# Synth.net
KiCad netlist of a schematic drawn in Altium Designer
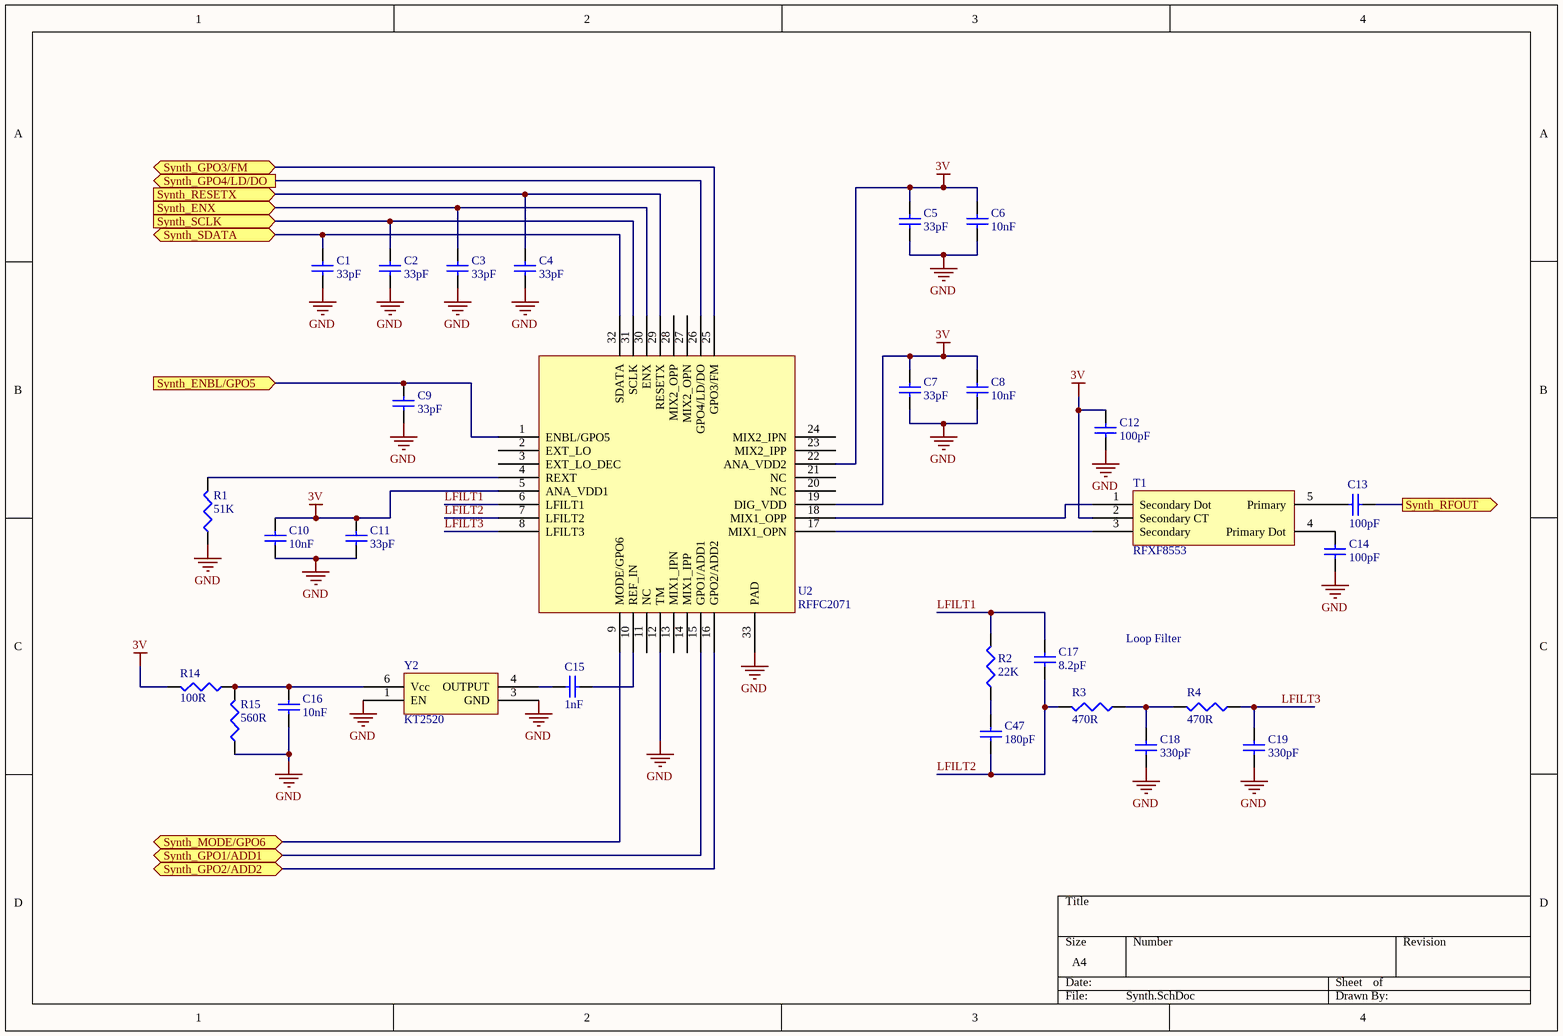
[diagram p0: Synth.SchDoc]

(export (version "E")
  (design (tool "Eeschema 10.0.6"))
  (components
    (comp (ref "C1")
      (value "33pF")
      (footprint "1608[0603]")
      (description "Capacitor (Semiconductor SIM Model)")
      (fields (field (name "Comment") "Cap Semi") (field (name "PUBLISHER") "Altium Limited"))
      (libsource (lib "Miscellaneous Devices") (part "Cap Semi"))
    )
    (comp (ref "C2")
      (value "33pF")
      (footprint "1608[0603]")
      (description "Capacitor (Semiconductor SIM Model)")
      (fields (field (name "Comment") "Cap Semi") (field (name "PUBLISHER") "Altium Limited"))
      (libsource (lib "Miscellaneous Devices") (part "Cap Semi"))
    )
    (comp (ref "C3")
      (value "33pF")
      (footprint "1608[0603]")
      (description "Capacitor (Semiconductor SIM Model)")
      (fields (field (name "Comment") "Cap Semi") (field (name "PUBLISHER") "Altium Limited"))
      (libsource (lib "Miscellaneous Devices") (part "Cap Semi"))
    )
    (comp (ref "C4")
      (value "33pF")
      (footprint "1608[0603]")
      (description "Capacitor (Semiconductor SIM Model)")
      (fields (field (name "Comment") "Cap Semi") (field (name "PUBLISHER") "Altium Limited"))
      (libsource (lib "Miscellaneous Devices") (part "Cap Semi"))
    )
    (comp (ref "C5")
      (value "33pF")
      (footprint "1608[0603]")
      (description "Capacitor (Semiconductor SIM Model)")
      (fields (field (name "Comment") "Cap Semi") (field (name "PUBLISHER") "Altium Limited"))
      (libsource (lib "Miscellaneous Devices") (part "Cap Semi"))
    )
    (comp (ref "C6")
      (value "10nF")
      (footprint "1608[0603]")
      (description "Capacitor (Semiconductor SIM Model)")
      (fields (field (name "Comment") "Cap Semi") (field (name "PUBLISHER") "Altium Limited"))
      (libsource (lib "Miscellaneous Devices") (part "Cap Semi"))
    )
    (comp (ref "C7")
      (value "33pF")
      (footprint "1608[0603]")
      (description "Capacitor (Semiconductor SIM Model)")
      (fields (field (name "Comment") "Cap Semi") (field (name "PUBLISHER") "Altium Limited"))
      (libsource (lib "Miscellaneous Devices") (part "Cap Semi"))
    )
    (comp (ref "C8")
      (value "10nF")
      (footprint "1608[0603]")
      (description "Capacitor (Semiconductor SIM Model)")
      (fields (field (name "Comment") "Cap Semi") (field (name "PUBLISHER") "Altium Limited"))
      (libsource (lib "Miscellaneous Devices") (part "Cap Semi"))
    )
    (comp (ref "C9")
      (value "33pF")
      (footprint "1608[0603]")
      (description "Capacitor (Semiconductor SIM Model)")
      (fields (field (name "Comment") "Cap Semi") (field (name "PUBLISHER") "Altium Limited"))
      (libsource (lib "Miscellaneous Devices") (part "Cap Semi"))
    )
    (comp (ref "C10")
      (value "10nF")
      (footprint "1608[0603]")
      (description "Capacitor (Semiconductor SIM Model)")
      (fields (field (name "Comment") "Cap Semi") (field (name "PUBLISHER") "Altium Limited"))
      (libsource (lib "Miscellaneous Devices") (part "Cap Semi"))
    )
    (comp (ref "C11")
      (value "33pF")
      (footprint "1608[0603]")
      (description "Capacitor (Semiconductor SIM Model)")
      (fields (field (name "Comment") "Cap Semi") (field (name "PUBLISHER") "Altium Limited"))
      (libsource (lib "Miscellaneous Devices") (part "Cap Semi"))
    )
    (comp (ref "C12")
      (value "100pF")
      (footprint "1608[0603]")
      (description "Capacitor (Semiconductor SIM Model)")
      (fields (field (name "Comment") "Cap Semi") (field (name "PUBLISHER") "Altium Limited"))
      (libsource (lib "Miscellaneous Devices") (part "Cap Semi"))
    )
    (comp (ref "C13")
      (value "100pF")
      (footprint "1608[0603]")
      (description "Capacitor (Semiconductor SIM Model)")
      (fields (field (name "Comment") "Cap Semi") (field (name "PUBLISHER") "Altium Limited"))
      (libsource (lib "Miscellaneous Devices") (part "Cap Semi"))
    )
    (comp (ref "C14")
      (value "100pF")
      (footprint "1608[0603]")
      (description "Capacitor (Semiconductor SIM Model)")
      (fields (field (name "Comment") "Cap Semi") (field (name "PUBLISHER") "Altium Limited"))
      (libsource (lib "Miscellaneous Devices") (part "Cap Semi"))
    )
    (comp (ref "C15")
      (value "1nF")
      (footprint "1608[0603]")
      (description "Capacitor (Semiconductor SIM Model)")
      (fields (field (name "Comment") "Cap Semi") (field (name "PUBLISHER") "Altium Limited"))
      (libsource (lib "Miscellaneous Devices") (part "Cap Semi"))
    )
    (comp (ref "C16")
      (value "10nF")
      (footprint "1608[0603]")
      (description "Capacitor (Semiconductor SIM Model)")
      (fields (field (name "Comment") "Cap Semi") (field (name "PUBLISHER") "Altium Limited"))
      (libsource (lib "Miscellaneous Devices") (part "Cap Semi"))
    )
    (comp (ref "C17")
      (value "8.2pF")
      (footprint "1608[0603]")
      (description "Capacitor (Semiconductor SIM Model)")
      (fields (field (name "Comment") "Cap Semi") (field (name "PUBLISHER") "Altium Limited"))
      (libsource (lib "Miscellaneous Devices") (part "Cap Semi"))
    )
    (comp (ref "C18")
      (value "330pF")
      (footprint "1608[0603]")
      (description "Capacitor (Semiconductor SIM Model)")
      (fields (field (name "Comment") "Cap Semi") (field (name "PUBLISHER") "Altium Limited"))
      (libsource (lib "Miscellaneous Devices") (part "Cap Semi"))
    )
    (comp (ref "C19")
      (value "330pF")
      (footprint "1608[0603]")
      (description "Capacitor (Semiconductor SIM Model)")
      (fields (field (name "Comment") "Cap Semi") (field (name "PUBLISHER") "Altium Limited"))
      (libsource (lib "Miscellaneous Devices") (part "Cap Semi"))
    )
    (comp (ref "C47")
      (value "180pF")
      (footprint "1608[0603]")
      (description "Capacitor (Semiconductor SIM Model)")
      (fields (field (name "Comment") "Cap Semi") (field (name "PUBLISHER") "Altium Limited"))
      (libsource (lib "Miscellaneous Devices") (part "Cap Semi"))
    )
    (comp (ref "R1")
      (value "51K")
      (footprint "J1-0603")
      (description "Resistor")
      (fields (field (name "Comment") "Res3") (field (name "PUBLISHER") "Altium Limited"))
      (libsource (lib "Miscellaneous Devices") (part "Res3"))
    )
    (comp (ref "R2")
      (value "22K")
      (footprint "J1-0603")
      (description "Resistor")
      (fields (field (name "Comment") "Res3") (field (name "PUBLISHER") "Altium Limited"))
      (libsource (lib "Miscellaneous Devices") (part "Res3"))
    )
    (comp (ref "R3")
      (value "470R")
      (footprint "J1-0603")
      (description "Resistor")
      (fields (field (name "Comment") "Res3") (field (name "PUBLISHER") "Altium Limited"))
      (libsource (lib "Miscellaneous Devices") (part "Res3"))
    )
    (comp (ref "R4")
      (value "470R")
      (footprint "J1-0603")
      (description "Resistor")
      (fields (field (name "Comment") "Res3") (field (name "PUBLISHER") "Altium Limited"))
      (libsource (lib "Miscellaneous Devices") (part "Res3"))
    )
    (comp (ref "R14")
      (value "100R")
      (footprint "J1-0603")
      (description "Resistor")
      (fields (field (name "Comment") "Res3") (field (name "PUBLISHER") "Altium Limited"))
      (libsource (lib "Miscellaneous Devices") (part "Res3"))
    )
    (comp (ref "R15")
      (value "560R")
      (footprint "J1-0603")
      (description "Resistor")
      (fields (field (name "Comment") "Res3") (field (name "PUBLISHER") "Altium Limited"))
      (libsource (lib "Miscellaneous Devices") (part "Res3"))
    )
    (comp (ref "T1")
      (value "RFXF8553")
      (footprint "RFXF8553")
      (description "1:4 SMT TRANSFORMER")
      (libsource (lib "Logic_RF_Component_Symbols") (part "RFXF8553"))
    )
    (comp (ref "U2")
      (value "RFFC2071")
      (footprint "QFN50P500X500-32WAL")
      (description "2.7GHz RF SYNTHESIZER/VCO WITH INTEGRATED RF MIXER")
      (libsource (lib "Logic_RF_Component_Symbols") (part "RFFC2071"))
    )
    (comp (ref "Y2")
      (value "KT2520")
      (footprint "KT2520")
      (description "Temperature-Compensated Crystal Oscillator (TCXO) KT2520")
      (libsource (lib "Logic_RF_Component_Symbols") (part "KT2520"))
    )
  )
  (nets
    (net (code "1") (name "/LFILT1") (class "Default")
      (node (ref "C17") (pin "2") (pinfunction "2_2") (pintype "passive"))
      (node (ref "R2") (pin "2") (pinfunction "2_2") (pintype "passive"))
      (node (ref "U2") (pin "6") (pinfunction "LFILT1_6") (pintype "passive"))
    )
    (net (code "2") (name "/LFILT2") (class "Default")
      (node (ref "C17") (pin "1") (pinfunction "1_1") (pintype "passive"))
      (node (ref "C47") (pin "1") (pinfunction "1_1") (pintype "passive"))
      (node (ref "R3") (pin "2") (pinfunction "2_2") (pintype "passive"))
      (node (ref "U2") (pin "7") (pinfunction "LFILT2_7") (pintype "passive"))
    )
    (net (code "3") (name "/LFILT3") (class "Default")
      (node (ref "C19") (pin "2") (pinfunction "2_2") (pintype "passive"))
      (node (ref "R4") (pin "1") (pinfunction "1_1") (pintype "passive"))
      (node (ref "U2") (pin "8") (pinfunction "LFILT3_8") (pintype "passive"))
    )
    (net (code "4") (name "/Synth_ENBL{slash}GPO5") (class "Default")
      (node (ref "C9") (pin "2") (pinfunction "2_2") (pintype "passive"))
      (node (ref "U2") (pin "1") (pinfunction "ENBL/GPO5_1") (pintype "passive"))
    )
    (net (code "5") (name "/Synth_ENX") (class "Default")
      (node (ref "C3") (pin "2") (pinfunction "2_2") (pintype "passive"))
      (node (ref "U2") (pin "30") (pinfunction "ENX_30") (pintype "passive"))
    )
    (net (code "6") (name "/Synth_GPO1{slash}ADD1") (class "Default")
      (node (ref "U2") (pin "15") (pinfunction "GPO1/ADD1_15") (pintype "passive"))
    )
    (net (code "7") (name "/Synth_GPO2{slash}ADD2") (class "Default")
      (node (ref "U2") (pin "16") (pinfunction "GPO2/ADD2_16") (pintype "passive"))
    )
    (net (code "8") (name "/Synth_GPO3{slash}FM") (class "Default")
      (node (ref "U2") (pin "25") (pinfunction "GPO3/FM_25") (pintype "passive"))
    )
    (net (code "9") (name "/Synth_GPO4{slash}LD{slash}DO") (class "Default")
      (node (ref "U2") (pin "26") (pinfunction "GPO4/LD/DO_26") (pintype "passive"))
    )
    (net (code "10") (name "/Synth_MODE{slash}GPO6") (class "Default")
      (node (ref "U2") (pin "9") (pinfunction "MODE/GPO6_9") (pintype "passive"))
    )
    (net (code "11") (name "/Synth_RESETX") (class "Default")
      (node (ref "C4") (pin "2") (pinfunction "2_2") (pintype "passive"))
      (node (ref "U2") (pin "29") (pinfunction "RESETX_29") (pintype "passive"))
    )
    (net (code "12") (name "/Synth_RFOUT") (class "Default")
      (node (ref "C13") (pin "2") (pinfunction "2_2") (pintype "passive"))
    )
    (net (code "13") (name "/Synth_SCLK") (class "Default")
      (node (ref "C2") (pin "2") (pinfunction "2_2") (pintype "passive"))
      (node (ref "U2") (pin "31") (pinfunction "SCLK_31") (pintype "passive"))
    )
    (net (code "14") (name "/Synth_SDATA") (class "Default")
      (node (ref "C1") (pin "2") (pinfunction "2_2") (pintype "passive"))
      (node (ref "U2") (pin "32") (pinfunction "SDATA_32") (pintype "passive"))
    )
    (net (code "15") (name "3V") (class "Default")
      (node (ref "C10") (pin "2") (pinfunction "2_2") (pintype "passive"))
      (node (ref "C11") (pin "2") (pinfunction "2_2") (pintype "passive"))
      (node (ref "C12") (pin "1") (pinfunction "1_1") (pintype "passive"))
      (node (ref "C5") (pin "1") (pinfunction "1_1") (pintype "passive"))
      (node (ref "C6") (pin "1") (pinfunction "1_1") (pintype "passive"))
      (node (ref "C7") (pin "1") (pinfunction "1_1") (pintype "passive"))
      (node (ref "C8") (pin "1") (pinfunction "1_1") (pintype "passive"))
      (node (ref "R14") (pin "2") (pinfunction "2_2") (pintype "passive"))
      (node (ref "T1") (pin "2") (pinfunction "Secondary_CT_2") (pintype "passive"))
      (node (ref "U2") (pin "19") (pinfunction "DIG_VDD_19") (pintype "passive"))
      (node (ref "U2") (pin "22") (pinfunction "ANA_VDD2_22") (pintype "passive"))
      (node (ref "U2") (pin "5") (pinfunction "ANA_VDD1_5") (pintype "passive"))
    )
    (net (code "16") (name "GND") (class "Default")
      (node (ref "C1") (pin "1") (pinfunction "1_1") (pintype "passive"))
      (node (ref "C10") (pin "1") (pinfunction "1_1") (pintype "passive"))
      (node (ref "C11") (pin "1") (pinfunction "1_1") (pintype "passive"))
      (node (ref "C12") (pin "2") (pinfunction "2_2") (pintype "passive"))
      (node (ref "C14") (pin "1") (pinfunction "1_1") (pintype "passive"))
      (node (ref "C16") (pin "1") (pinfunction "1_1") (pintype "passive"))
      (node (ref "C18") (pin "1") (pinfunction "1_1") (pintype "passive"))
      (node (ref "C19") (pin "1") (pinfunction "1_1") (pintype "passive"))
      (node (ref "C2") (pin "1") (pinfunction "1_1") (pintype "passive"))
      (node (ref "C3") (pin "1") (pinfunction "1_1") (pintype "passive"))
      (node (ref "C4") (pin "1") (pinfunction "1_1") (pintype "passive"))
      (node (ref "C5") (pin "2") (pinfunction "2_2") (pintype "passive"))
      (node (ref "C6") (pin "2") (pinfunction "2_2") (pintype "passive"))
      (node (ref "C7") (pin "2") (pinfunction "2_2") (pintype "passive"))
      (node (ref "C8") (pin "2") (pinfunction "2_2") (pintype "passive"))
      (node (ref "C9") (pin "1") (pinfunction "1_1") (pintype "passive"))
      (node (ref "R1") (pin "1") (pinfunction "1_1") (pintype "passive"))
      (node (ref "R15") (pin "1") (pinfunction "1_1") (pintype "passive"))
      (node (ref "U2") (pin "12") (pinfunction "TM_12") (pintype "passive"))
      (node (ref "U2") (pin "33") (pinfunction "PAD_33") (pintype "passive"))
      (node (ref "Y2") (pin "1") (pinfunction "EN_1") (pintype "passive"))
      (node (ref "Y2") (pin "3") (pinfunction "GND_3") (pintype "passive"))
    )
    (net (code "17") (name "Net-(C18-Pad2)") (class "Default")
      (node (ref "C18") (pin "2") (pinfunction "2_2") (pintype "passive"))
      (node (ref "R3") (pin "1") (pinfunction "1_1") (pintype "passive"))
      (node (ref "R4") (pin "2") (pinfunction "2_2") (pintype "passive"))
    )
    (net (code "18") (name "Net-(C47-Pad2)") (class "Default")
      (node (ref "C47") (pin "2") (pinfunction "2_2") (pintype "passive"))
      (node (ref "R2") (pin "1") (pinfunction "1_1") (pintype "passive"))
    )
    (net (code "19") (name "Net-(T1-Primary)") (class "Default")
      (node (ref "C13") (pin "1") (pinfunction "1_1") (pintype "passive"))
      (node (ref "T1") (pin "5") (pinfunction "Primary_5") (pintype "passive"))
    )
    (net (code "20") (name "Net-(T1-Primary_Dot)") (class "Default")
      (node (ref "C14") (pin "2") (pinfunction "2_2") (pintype "passive"))
      (node (ref "T1") (pin "4") (pinfunction "Primary_Dot_4") (pintype "passive"))
    )
    (net (code "21") (name "Net-(T1-Secondary)") (class "Default")
      (node (ref "T1") (pin "3") (pinfunction "Secondary_3") (pintype "passive"))
      (node (ref "U2") (pin "17") (pinfunction "MIX1_OPN_17") (pintype "passive"))
    )
    (net (code "22") (name "Net-(T1-Secondary_Dot)") (class "Default")
      (node (ref "T1") (pin "1") (pinfunction "Secondary_Dot_1") (pintype "passive"))
      (node (ref "U2") (pin "18") (pinfunction "MIX1_OPP_18") (pintype "passive"))
    )
    (net (code "23") (name "Net-(U2-REF_IN)") (class "Default")
      (node (ref "C15") (pin "1") (pinfunction "1_1") (pintype "passive"))
      (node (ref "U2") (pin "10") (pinfunction "REF_IN_10") (pintype "passive"))
    )
    (net (code "24") (name "Net-(U2-REXT)") (class "Default")
      (node (ref "R1") (pin "2") (pinfunction "2_2") (pintype "passive"))
      (node (ref "U2") (pin "4") (pinfunction "REXT_4") (pintype "passive"))
    )
    (net (code "25") (name "Net-(Y2-OUTPUT)") (class "Default")
      (node (ref "C15") (pin "2") (pinfunction "2_2") (pintype "passive"))
      (node (ref "Y2") (pin "4") (pinfunction "OUTPUT_4") (pintype "passive"))
    )
    (net (code "26") (name "Net-(Y2-Vcc)") (class "Default")
      (node (ref "C16") (pin "2") (pinfunction "2_2") (pintype "passive"))
      (node (ref "R14") (pin "1") (pinfunction "1_1") (pintype "passive"))
      (node (ref "R15") (pin "2") (pinfunction "2_2") (pintype "passive"))
      (node (ref "Y2") (pin "6") (pinfunction "Vcc_6") (pintype "passive"))
    )
    (net (code "27") (name "unconnected-(U2-EXT_LO-Pad2)") (class "Default")
      (node (ref "U2") (pin "2") (pinfunction "EXT_LO_2") (pintype "passive"))
    )
    (net (code "28") (name "unconnected-(U2-EXT_LO_DEC-Pad3)") (class "Default")
      (node (ref "U2") (pin "3") (pinfunction "EXT_LO_DEC_3") (pintype "passive"))
    )
    (net (code "29") (name "unconnected-(U2-MIX1_IPN-Pad13)") (class "Default")
      (node (ref "U2") (pin "13") (pinfunction "MIX1_IPN_13") (pintype "passive"))
    )
    (net (code "30") (name "unconnected-(U2-MIX1_IPP-Pad14)") (class "Default")
      (node (ref "U2") (pin "14") (pinfunction "MIX1_IPP_14") (pintype "passive"))
    )
    (net (code "31") (name "unconnected-(U2-MIX2_IPN-Pad24)") (class "Default")
      (node (ref "U2") (pin "24") (pinfunction "MIX2_IPN_24") (pintype "passive"))
    )
    (net (code "32") (name "unconnected-(U2-MIX2_IPP-Pad23)") (class "Default")
      (node (ref "U2") (pin "23") (pinfunction "MIX2_IPP_23") (pintype "passive"))
    )
    (net (code "33") (name "unconnected-(U2-MIX2_OPN-Pad27)") (class "Default")
      (node (ref "U2") (pin "27") (pinfunction "MIX2_OPN_27") (pintype "passive"))
    )
    (net (code "34") (name "unconnected-(U2-MIX2_OPP-Pad28)") (class "Default")
      (node (ref "U2") (pin "28") (pinfunction "MIX2_OPP_28") (pintype "passive"))
    )
    (net (code "35") (name "unconnected-(U2-NC-Pad11)") (class "Default")
      (node (ref "U2") (pin "11") (pinfunction "NC_11") (pintype "passive"))
    )
    (net (code "36") (name "unconnected-(U2-NC-Pad20)") (class "Default")
      (node (ref "U2") (pin "20") (pinfunction "NC_20") (pintype "passive"))
    )
    (net (code "37") (name "unconnected-(U2-NC-Pad21)") (class "Default")
      (node (ref "U2") (pin "21") (pinfunction "NC_21") (pintype "passive"))
    )
  )
)
